# PCB_v1_0.net
KiCad netlist of a schematic drawn in EAGLE
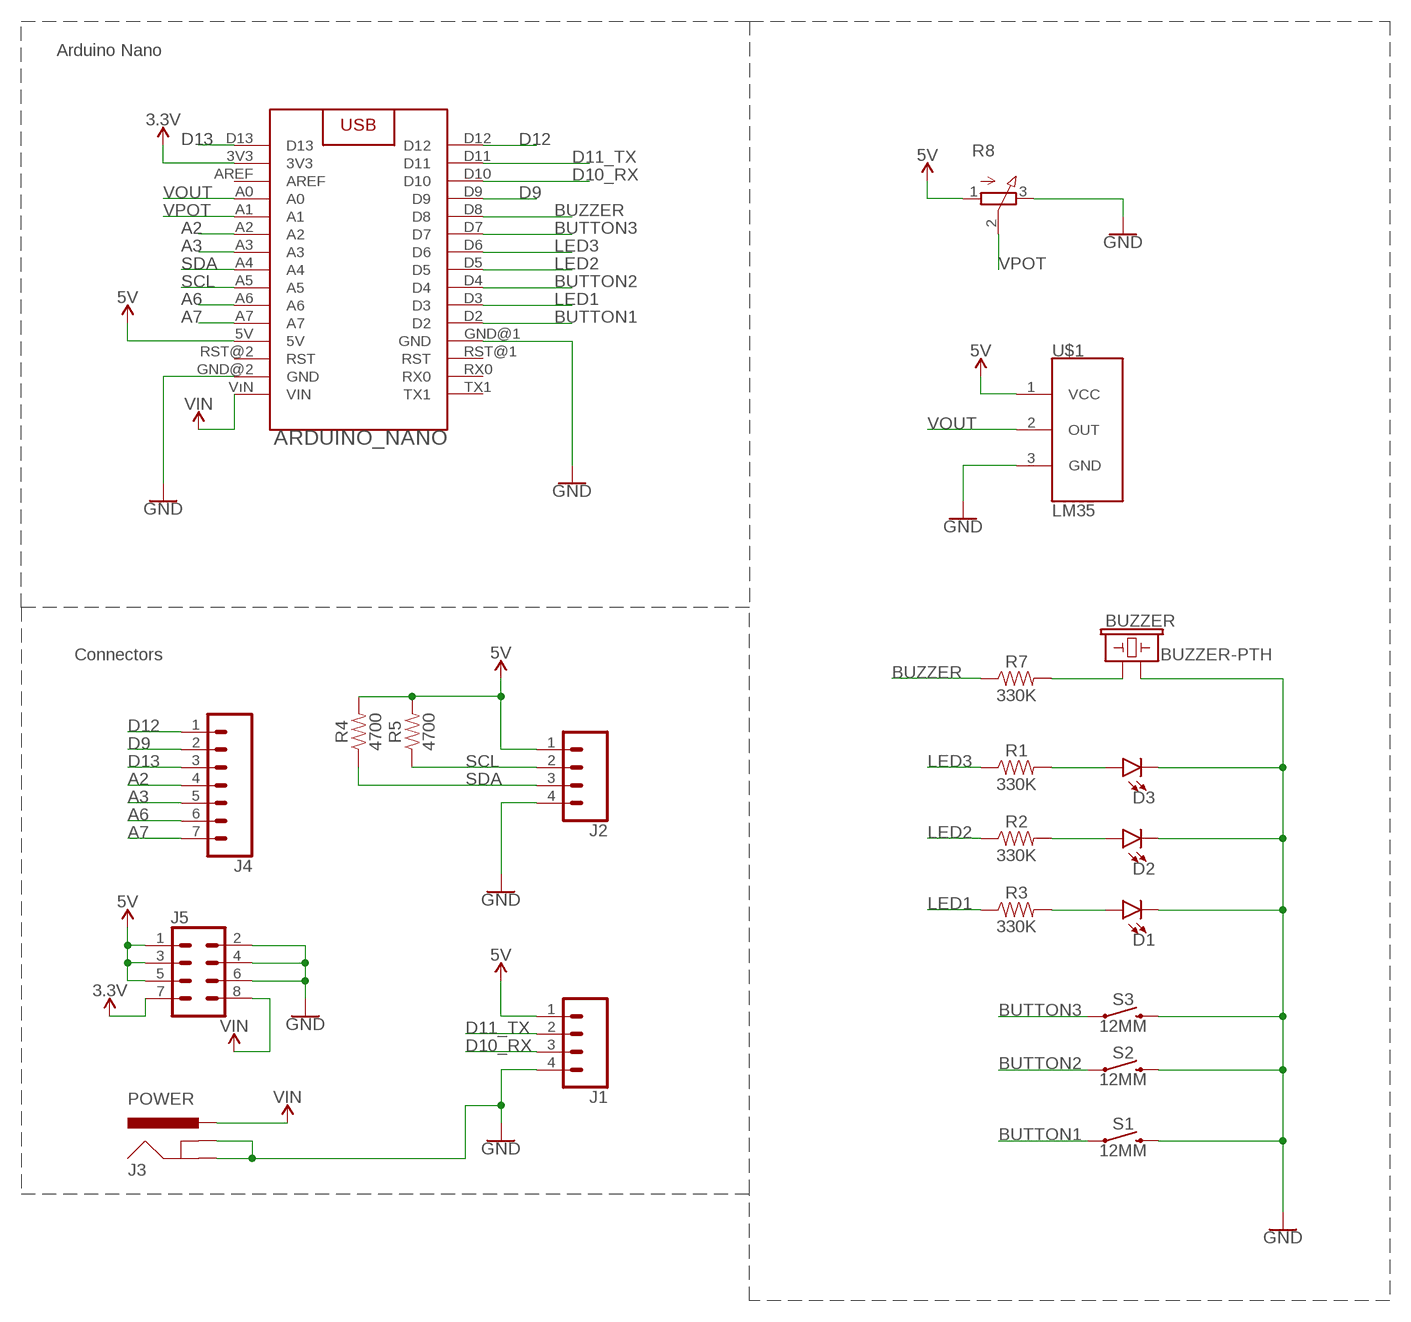
[diagram p0: schematic, sheet 1]

(export (version "E")
  (design (tool "Eeschema 10.0.6"))
  (components
    (comp (ref "ARDUINO_NANO")
      (value "ARDUINO_NANO")
      (footprint "eagle-import:ARDUINO_NANO")
      (libsource (lib "eagle-import") (part "ARDUINO_NANO"))
    )
    (comp (ref "BUZZER")
      (value "BUZZER-PTH")
      (footprint "eagle-import:BUZZER-12MM")
      (libsource (lib "eagle-import") (part "BUZZER-PTH"))
    )
    (comp (ref "D1")
      (value "LED-3MM-NO_SILK")
      (footprint "eagle-import:LED_3MM-NS")
      (libsource (lib "eagle-import") (part "LED-3MM-NO_SILK"))
    )
    (comp (ref "D2")
      (value "LED-3MM-NO_SILK")
      (footprint "eagle-import:LED_3MM-NS")
      (libsource (lib "eagle-import") (part "LED-3MM-NO_SILK"))
    )
    (comp (ref "D3")
      (value "LED-3MM-NO_SILK")
      (footprint "eagle-import:LED_3MM-NS")
      (libsource (lib "eagle-import") (part "LED-3MM-NO_SILK"))
    )
    (comp (ref "J1")
      (value "CONN_04PTH")
      (footprint "eagle-import:1X04")
      (libsource (lib "eagle-import") (part "CONN_04PTH"))
    )
    (comp (ref "J2")
      (value "CONN_04PTH")
      (footprint "eagle-import:1X04")
      (libsource (lib "eagle-import") (part "CONN_04PTH"))
    )
    (comp (ref "J3")
      (value "POWER")
      (footprint "eagle-import:POWER_JACK_PTH")
      (libsource (lib "eagle-import") (part "POWER_JACK"))
    )
    (comp (ref "J4")
      (value "CONN_07")
      (footprint "eagle-import:1X07")
      (libsource (lib "eagle-import") (part "CONN_07"))
    )
    (comp (ref "J5")
      (value "CONN_04X2")
      (footprint "eagle-import:2X4")
      (libsource (lib "eagle-import") (part "CONN_04X2"))
    )
    (comp (ref "R1")
      (value "330K")
      (footprint "eagle-import:AXIAL-0.3")
      (libsource (lib "eagle-import") (part "1KOHM-HORIZ-1/4W-5%"))
    )
    (comp (ref "R2")
      (value "330K")
      (footprint "eagle-import:AXIAL-0.3")
      (libsource (lib "eagle-import") (part "1KOHM-HORIZ-1/4W-5%"))
    )
    (comp (ref "R3")
      (value "330K")
      (footprint "eagle-import:AXIAL-0.3")
      (libsource (lib "eagle-import") (part "1KOHM-HORIZ-1/4W-5%"))
    )
    (comp (ref "R4")
      (value "4700")
      (footprint "eagle-import:AXIAL-0.3")
      (libsource (lib "eagle-import") (part "1KOHM-HORIZ-1/4W-5%"))
    )
    (comp (ref "R5")
      (value "4700")
      (footprint "eagle-import:AXIAL-0.3")
      (libsource (lib "eagle-import") (part "1KOHM-HORIZ-1/4W-5%"))
    )
    (comp (ref "R7")
      (value "330K")
      (footprint "eagle-import:AXIAL-0.3")
      (libsource (lib "eagle-import") (part "1KOHM-HORIZ-1/4W-5%"))
    )
    (comp (ref "R8")
      (value "3RP/1610N")
      (footprint "eagle-import:3RP_1610N")
      (libsource (lib "eagle-import") (part "3RP/1610N"))
    )
    (comp (ref "S1")
      (value "12MM")
      (footprint "eagle-import:TACTILE_SWITCH_PTH_12MM")
      (libsource (lib "eagle-import") (part "MOMENTARY-SWITCH-SPST-PTH-12MM"))
    )
    (comp (ref "S2")
      (value "12MM")
      (footprint "eagle-import:TACTILE_SWITCH_PTH_12MM")
      (libsource (lib "eagle-import") (part "MOMENTARY-SWITCH-SPST-PTH-12MM"))
    )
    (comp (ref "S3")
      (value "12MM")
      (footprint "eagle-import:TACTILE_SWITCH_PTH_12MM")
      (libsource (lib "eagle-import") (part "MOMENTARY-SWITCH-SPST-PTH-12MM"))
    )
    (comp (ref "U$1")
      (value "LM35")
      (footprint "eagle-import:TO-92")
      (libsource (lib "eagle-import") (part "LM35"))
    )
  )
  (nets
    (net (code "1") (name "/A2") (class "Default")
      (node (ref "ARDUINO_NANO") (pin "A2") (pinfunction "A2_A2") (pintype "bidirectional"))
      (node (ref "J4") (pin "4") (pinfunction "4_4") (pintype "passive"))
    )
    (net (code "2") (name "/A3") (class "Default")
      (node (ref "ARDUINO_NANO") (pin "A3") (pinfunction "A3_A3") (pintype "bidirectional"))
      (node (ref "J4") (pin "5") (pinfunction "5_5") (pintype "passive"))
    )
    (net (code "3") (name "/A6") (class "Default")
      (node (ref "ARDUINO_NANO") (pin "A6") (pinfunction "A6_A6") (pintype "bidirectional"))
      (node (ref "J4") (pin "6") (pinfunction "6_6") (pintype "passive"))
    )
    (net (code "4") (name "/A7") (class "Default")
      (node (ref "ARDUINO_NANO") (pin "A7") (pinfunction "A7_A7") (pintype "bidirectional"))
      (node (ref "J4") (pin "7") (pinfunction "7_7") (pintype "passive"))
    )
    (net (code "5") (name "/BUTTON1") (class "Default")
      (node (ref "ARDUINO_NANO") (pin "D2") (pinfunction "D2_D2") (pintype "bidirectional"))
      (node (ref "S1") (pin "1") (pinfunction "1_1") (pintype "passive"))
    )
    (net (code "6") (name "/BUTTON2") (class "Default")
      (node (ref "ARDUINO_NANO") (pin "D4") (pinfunction "D4_D4") (pintype "bidirectional"))
      (node (ref "S2") (pin "1") (pinfunction "1_1") (pintype "passive"))
    )
    (net (code "7") (name "/BUTTON3") (class "Default")
      (node (ref "ARDUINO_NANO") (pin "D7") (pinfunction "D7_D7") (pintype "bidirectional"))
      (node (ref "S3") (pin "1") (pinfunction "1_1") (pintype "passive"))
    )
    (net (code "8") (name "/BUZZER") (class "Default")
      (node (ref "ARDUINO_NANO") (pin "D8") (pinfunction "D8_D8") (pintype "bidirectional"))
      (node (ref "R7") (pin "P$1") (pinfunction "1_P$1") (pintype "passive"))
    )
    (net (code "9") (name "/D9") (class "Default")
      (node (ref "ARDUINO_NANO") (pin "D9") (pinfunction "D9_D9") (pintype "bidirectional"))
      (node (ref "J4") (pin "2") (pinfunction "2_2") (pintype "passive"))
    )
    (net (code "10") (name "/D10_RX") (class "Default")
      (node (ref "ARDUINO_NANO") (pin "D10") (pinfunction "D10_D10") (pintype "bidirectional"))
      (node (ref "J1") (pin "3") (pinfunction "3_3") (pintype "passive"))
    )
    (net (code "11") (name "/D11_TX") (class "Default")
      (node (ref "ARDUINO_NANO") (pin "D11") (pinfunction "D11_D11") (pintype "bidirectional"))
      (node (ref "J1") (pin "2") (pinfunction "2_2") (pintype "passive"))
    )
    (net (code "12") (name "/D12") (class "Default")
      (node (ref "ARDUINO_NANO") (pin "D12") (pinfunction "D12_D12") (pintype "bidirectional"))
      (node (ref "J4") (pin "1") (pinfunction "1_1") (pintype "passive"))
    )
    (net (code "13") (name "/D13") (class "Default")
      (node (ref "ARDUINO_NANO") (pin "D13") (pinfunction "D13_D13") (pintype "bidirectional"))
      (node (ref "J4") (pin "3") (pinfunction "3_3") (pintype "passive"))
    )
    (net (code "14") (name "/LED1") (class "Default")
      (node (ref "ARDUINO_NANO") (pin "D3") (pinfunction "D3_D3") (pintype "bidirectional"))
      (node (ref "R3") (pin "P$1") (pinfunction "1_P$1") (pintype "passive"))
    )
    (net (code "15") (name "/LED2") (class "Default")
      (node (ref "ARDUINO_NANO") (pin "D5") (pinfunction "D5_D5") (pintype "bidirectional"))
      (node (ref "R2") (pin "P$1") (pinfunction "1_P$1") (pintype "passive"))
    )
    (net (code "16") (name "/LED3") (class "Default")
      (node (ref "ARDUINO_NANO") (pin "D6") (pinfunction "D6_D6") (pintype "bidirectional"))
      (node (ref "R1") (pin "P$1") (pinfunction "1_P$1") (pintype "passive"))
    )
    (net (code "17") (name "/SCL") (class "Default")
      (node (ref "ARDUINO_NANO") (pin "A5") (pinfunction "A5_A5") (pintype "bidirectional"))
      (node (ref "J2") (pin "2") (pinfunction "2_2") (pintype "passive"))
      (node (ref "R5") (pin "P$1") (pinfunction "1_P$1") (pintype "passive"))
    )
    (net (code "18") (name "/SDA") (class "Default")
      (node (ref "ARDUINO_NANO") (pin "A4") (pinfunction "A4_A4") (pintype "bidirectional"))
      (node (ref "J2") (pin "3") (pinfunction "3_3") (pintype "passive"))
      (node (ref "R4") (pin "P$1") (pinfunction "1_P$1") (pintype "passive"))
    )
    (net (code "19") (name "/VOUT") (class "Default")
      (node (ref "ARDUINO_NANO") (pin "A0") (pinfunction "A0_A0") (pintype "bidirectional"))
      (node (ref "U$1") (pin "2") (pinfunction "OUT_2") (pintype "bidirectional"))
    )
    (net (code "20") (name "/VPOT") (class "Default")
      (node (ref "ARDUINO_NANO") (pin "A1") (pinfunction "A1_A1") (pintype "bidirectional"))
      (node (ref "R8") (pin "2") (pinfunction "S_2") (pintype "passive"))
    )
    (net (code "21") (name "3.3V") (class "Default")
      (node (ref "ARDUINO_NANO") (pin "3V3") (pinfunction "3V3_3V3") (pintype "bidirectional"))
      (node (ref "J5") (pin "7") (pinfunction "7_7") (pintype "passive"))
    )
    (net (code "22") (name "5V") (class "Default")
      (node (ref "ARDUINO_NANO") (pin "5V") (pinfunction "5V_5V") (pintype "bidirectional"))
      (node (ref "J1") (pin "1") (pinfunction "1_1") (pintype "passive"))
      (node (ref "J2") (pin "1") (pinfunction "1_1") (pintype "passive"))
      (node (ref "J5") (pin "1") (pinfunction "1_1") (pintype "passive"))
      (node (ref "J5") (pin "3") (pinfunction "3_3") (pintype "passive"))
      (node (ref "J5") (pin "5") (pinfunction "5_5") (pintype "passive"))
      (node (ref "R4") (pin "P$2") (pinfunction "2_P$2") (pintype "passive"))
      (node (ref "R5") (pin "P$2") (pinfunction "2_P$2") (pintype "passive"))
      (node (ref "R8") (pin "1") (pinfunction "A_1") (pintype "passive"))
      (node (ref "U$1") (pin "1") (pinfunction "VCC_1") (pintype "bidirectional"))
    )
    (net (code "23") (name "GND") (class "Default")
      (node (ref "ARDUINO_NANO") (pin "GND@1") (pinfunction "GND_GND@1") (pintype "bidirectional"))
      (node (ref "ARDUINO_NANO") (pin "GND@2") (pinfunction "GND_GND@2") (pintype "bidirectional"))
      (node (ref "BUZZER") (pin "-") (pinfunction "2_-") (pintype "passive"))
      (node (ref "D1") (pin "K") (pinfunction "C_K") (pintype "passive"))
      (node (ref "D2") (pin "K") (pinfunction "C_K") (pintype "passive"))
      (node (ref "D3") (pin "K") (pinfunction "C_K") (pintype "passive"))
      (node (ref "J1") (pin "4") (pinfunction "4_4") (pintype "passive"))
      (node (ref "J2") (pin "4") (pinfunction "4_4") (pintype "passive"))
      (node (ref "J3") (pin "GND") (pinfunction "GND_GND") (pintype "bidirectional"))
      (node (ref "J3") (pin "GNDBREAK") (pinfunction "GNDBREAK_GNDBREAK") (pintype "bidirectional"))
      (node (ref "J5") (pin "2") (pinfunction "2_2") (pintype "passive"))
      (node (ref "J5") (pin "4") (pinfunction "4_4") (pintype "passive"))
      (node (ref "J5") (pin "6") (pinfunction "6_6") (pintype "passive"))
      (node (ref "R8") (pin "3") (pinfunction "E_3") (pintype "passive"))
      (node (ref "S1") (pin "3") (pinfunction "2_3") (pintype "passive"))
      (node (ref "S2") (pin "3") (pinfunction "2_3") (pintype "passive"))
      (node (ref "S3") (pin "3") (pinfunction "2_3") (pintype "passive"))
      (node (ref "U$1") (pin "3") (pinfunction "GND_3") (pintype "bidirectional"))
    )
    (net (code "24") (name "Net-(BUZZER-1)") (class "Default")
      (node (ref "BUZZER") (pin "+") (pinfunction "1_+") (pintype "passive"))
      (node (ref "R7") (pin "P$2") (pinfunction "2_P$2") (pintype "passive"))
    )
    (net (code "25") (name "Net-(R1-2)") (class "Default")
      (node (ref "D3") (pin "A") (pinfunction "A_A") (pintype "passive"))
      (node (ref "R1") (pin "P$2") (pinfunction "2_P$2") (pintype "passive"))
    )
    (net (code "26") (name "Net-(R2-2)") (class "Default")
      (node (ref "D2") (pin "A") (pinfunction "A_A") (pintype "passive"))
      (node (ref "R2") (pin "P$2") (pinfunction "2_P$2") (pintype "passive"))
    )
    (net (code "27") (name "Net-(R3-2)") (class "Default")
      (node (ref "D1") (pin "A") (pinfunction "A_A") (pintype "passive"))
      (node (ref "R3") (pin "P$2") (pinfunction "2_P$2") (pintype "passive"))
    )
    (net (code "28") (name "VIN") (class "Default")
      (node (ref "ARDUINO_NANO") (pin "VıN") (pinfunction "VIN_VıN") (pintype "bidirectional"))
      (node (ref "J3") (pin "PWR") (pinfunction "PWR_PWR") (pintype "bidirectional"))
      (node (ref "J5") (pin "8") (pinfunction "8_8") (pintype "passive"))
    )
    (net (code "29") (name "unconnected-(ARDUINO_NANO-PadAREF)") (class "Default")
      (node (ref "ARDUINO_NANO") (pin "AREF") (pinfunction "AREF_AREF") (pintype "bidirectional"))
    )
    (net (code "30") (name "unconnected-(ARDUINO_NANO-PadRX0)") (class "Default")
      (node (ref "ARDUINO_NANO") (pin "RX0") (pinfunction "RX0_RX0") (pintype "bidirectional"))
    )
    (net (code "31") (name "unconnected-(ARDUINO_NANO-PadTX1)") (class "Default")
      (node (ref "ARDUINO_NANO") (pin "TX1") (pinfunction "TX1_TX1") (pintype "bidirectional"))
    )
    (net (code "32") (name "unconnected-(ARDUINO_NANO-RST-PadRST@1)") (class "Default")
      (node (ref "ARDUINO_NANO") (pin "RST@1") (pinfunction "RST_RST@1") (pintype "bidirectional"))
    )
    (net (code "33") (name "unconnected-(ARDUINO_NANO-RST-PadRST@2)") (class "Default")
      (node (ref "ARDUINO_NANO") (pin "RST@2") (pinfunction "RST_RST@2") (pintype "bidirectional"))
    )
  )
)
